# untitled.net
KiCad netlist of a schematic drawn in EAGLE
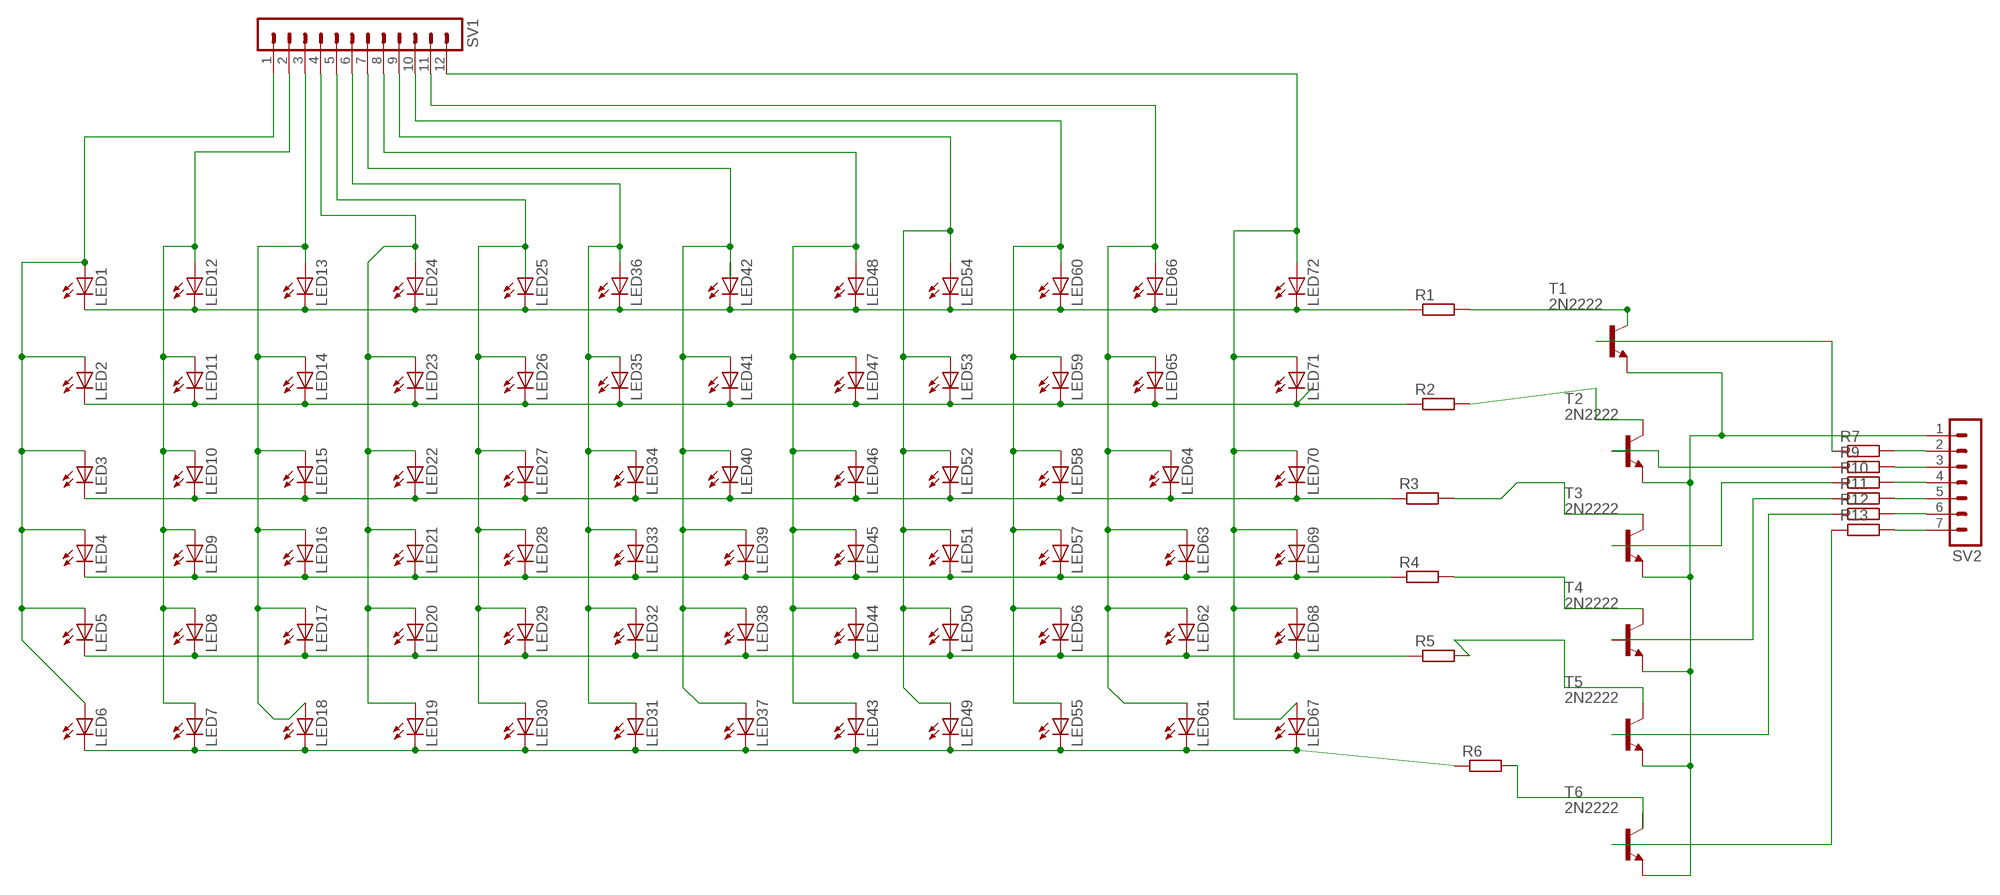
[diagram p0: schematic, sheet 1]

(export (version "E")
  (design (tool "Eeschema 10.0.6"))
  (components
    (comp (ref "LED1")
      (value "LED5MM")
      (footprint "eagle-import:LED5MM")
      (libsource (lib "eagle-import") (part "LED5MM"))
    )
    (comp (ref "LED2")
      (value "LED5MM")
      (footprint "eagle-import:LED5MM")
      (libsource (lib "eagle-import") (part "LED5MM"))
    )
    (comp (ref "LED3")
      (value "LED5MM")
      (footprint "eagle-import:LED5MM")
      (libsource (lib "eagle-import") (part "LED5MM"))
    )
    (comp (ref "LED4")
      (value "LED5MM")
      (footprint "eagle-import:LED5MM")
      (libsource (lib "eagle-import") (part "LED5MM"))
    )
    (comp (ref "LED5")
      (value "LED5MM")
      (footprint "eagle-import:LED5MM")
      (libsource (lib "eagle-import") (part "LED5MM"))
    )
    (comp (ref "LED6")
      (value "LED5MM")
      (footprint "eagle-import:LED5MM")
      (libsource (lib "eagle-import") (part "LED5MM"))
    )
    (comp (ref "LED7")
      (value "LED5MM")
      (footprint "eagle-import:LED5MM")
      (libsource (lib "eagle-import") (part "LED5MM"))
    )
    (comp (ref "LED8")
      (value "LED5MM")
      (footprint "eagle-import:LED5MM")
      (libsource (lib "eagle-import") (part "LED5MM"))
    )
    (comp (ref "LED9")
      (value "LED5MM")
      (footprint "eagle-import:LED5MM")
      (libsource (lib "eagle-import") (part "LED5MM"))
    )
    (comp (ref "LED10")
      (value "LED5MM")
      (footprint "eagle-import:LED5MM")
      (libsource (lib "eagle-import") (part "LED5MM"))
    )
    (comp (ref "LED11")
      (value "LED5MM")
      (footprint "eagle-import:LED5MM")
      (libsource (lib "eagle-import") (part "LED5MM"))
    )
    (comp (ref "LED12")
      (value "LED5MM")
      (footprint "eagle-import:LED5MM")
      (libsource (lib "eagle-import") (part "LED5MM"))
    )
    (comp (ref "LED13")
      (value "LED5MM")
      (footprint "eagle-import:LED5MM")
      (libsource (lib "eagle-import") (part "LED5MM"))
    )
    (comp (ref "LED14")
      (value "LED5MM")
      (footprint "eagle-import:LED5MM")
      (libsource (lib "eagle-import") (part "LED5MM"))
    )
    (comp (ref "LED15")
      (value "LED5MM")
      (footprint "eagle-import:LED5MM")
      (libsource (lib "eagle-import") (part "LED5MM"))
    )
    (comp (ref "LED16")
      (value "LED5MM")
      (footprint "eagle-import:LED5MM")
      (libsource (lib "eagle-import") (part "LED5MM"))
    )
    (comp (ref "LED17")
      (value "LED5MM")
      (footprint "eagle-import:LED5MM")
      (libsource (lib "eagle-import") (part "LED5MM"))
    )
    (comp (ref "LED18")
      (value "LED5MM")
      (footprint "eagle-import:LED5MM")
      (libsource (lib "eagle-import") (part "LED5MM"))
    )
    (comp (ref "LED19")
      (value "LED5MM")
      (footprint "eagle-import:LED5MM")
      (libsource (lib "eagle-import") (part "LED5MM"))
    )
    (comp (ref "LED20")
      (value "LED5MM")
      (footprint "eagle-import:LED5MM")
      (libsource (lib "eagle-import") (part "LED5MM"))
    )
    (comp (ref "LED21")
      (value "LED5MM")
      (footprint "eagle-import:LED5MM")
      (libsource (lib "eagle-import") (part "LED5MM"))
    )
    (comp (ref "LED22")
      (value "LED5MM")
      (footprint "eagle-import:LED5MM")
      (libsource (lib "eagle-import") (part "LED5MM"))
    )
    (comp (ref "LED23")
      (value "LED5MM")
      (footprint "eagle-import:LED5MM")
      (libsource (lib "eagle-import") (part "LED5MM"))
    )
    (comp (ref "LED24")
      (value "LED5MM")
      (footprint "eagle-import:LED5MM")
      (libsource (lib "eagle-import") (part "LED5MM"))
    )
    (comp (ref "LED25")
      (value "LED5MM")
      (footprint "eagle-import:LED5MM")
      (libsource (lib "eagle-import") (part "LED5MM"))
    )
    (comp (ref "LED26")
      (value "LED5MM")
      (footprint "eagle-import:LED5MM")
      (libsource (lib "eagle-import") (part "LED5MM"))
    )
    (comp (ref "LED27")
      (value "LED5MM")
      (footprint "eagle-import:LED5MM")
      (libsource (lib "eagle-import") (part "LED5MM"))
    )
    (comp (ref "LED28")
      (value "LED5MM")
      (footprint "eagle-import:LED5MM")
      (libsource (lib "eagle-import") (part "LED5MM"))
    )
    (comp (ref "LED29")
      (value "LED5MM")
      (footprint "eagle-import:LED5MM")
      (libsource (lib "eagle-import") (part "LED5MM"))
    )
    (comp (ref "LED30")
      (value "LED5MM")
      (footprint "eagle-import:LED5MM")
      (libsource (lib "eagle-import") (part "LED5MM"))
    )
    (comp (ref "LED31")
      (value "LED5MM")
      (footprint "eagle-import:LED5MM")
      (libsource (lib "eagle-import") (part "LED5MM"))
    )
    (comp (ref "LED32")
      (value "LED5MM")
      (footprint "eagle-import:LED5MM")
      (libsource (lib "eagle-import") (part "LED5MM"))
    )
    (comp (ref "LED33")
      (value "LED5MM")
      (footprint "eagle-import:LED5MM")
      (libsource (lib "eagle-import") (part "LED5MM"))
    )
    (comp (ref "LED34")
      (value "LED5MM")
      (footprint "eagle-import:LED5MM")
      (libsource (lib "eagle-import") (part "LED5MM"))
    )
    (comp (ref "LED35")
      (value "LED5MM")
      (footprint "eagle-import:LED5MM")
      (libsource (lib "eagle-import") (part "LED5MM"))
    )
    (comp (ref "LED36")
      (value "LED5MM")
      (footprint "eagle-import:LED5MM")
      (libsource (lib "eagle-import") (part "LED5MM"))
    )
    (comp (ref "LED37")
      (value "LED5MM")
      (footprint "eagle-import:LED5MM")
      (libsource (lib "eagle-import") (part "LED5MM"))
    )
    (comp (ref "LED38")
      (value "LED5MM")
      (footprint "eagle-import:LED5MM")
      (libsource (lib "eagle-import") (part "LED5MM"))
    )
    (comp (ref "LED39")
      (value "LED5MM")
      (footprint "eagle-import:LED5MM")
      (libsource (lib "eagle-import") (part "LED5MM"))
    )
    (comp (ref "LED40")
      (value "LED5MM")
      (footprint "eagle-import:LED5MM")
      (libsource (lib "eagle-import") (part "LED5MM"))
    )
    (comp (ref "LED41")
      (value "LED5MM")
      (footprint "eagle-import:LED5MM")
      (libsource (lib "eagle-import") (part "LED5MM"))
    )
    (comp (ref "LED42")
      (value "LED5MM")
      (footprint "eagle-import:LED5MM")
      (libsource (lib "eagle-import") (part "LED5MM"))
    )
    (comp (ref "LED43")
      (value "LED5MM")
      (footprint "eagle-import:LED5MM")
      (libsource (lib "eagle-import") (part "LED5MM"))
    )
    (comp (ref "LED44")
      (value "LED5MM")
      (footprint "eagle-import:LED5MM")
      (libsource (lib "eagle-import") (part "LED5MM"))
    )
    (comp (ref "LED45")
      (value "LED5MM")
      (footprint "eagle-import:LED5MM")
      (libsource (lib "eagle-import") (part "LED5MM"))
    )
    (comp (ref "LED46")
      (value "LED5MM")
      (footprint "eagle-import:LED5MM")
      (libsource (lib "eagle-import") (part "LED5MM"))
    )
    (comp (ref "LED47")
      (value "LED5MM")
      (footprint "eagle-import:LED5MM")
      (libsource (lib "eagle-import") (part "LED5MM"))
    )
    (comp (ref "LED48")
      (value "LED5MM")
      (footprint "eagle-import:LED5MM")
      (libsource (lib "eagle-import") (part "LED5MM"))
    )
    (comp (ref "LED49")
      (value "LED5MM")
      (footprint "eagle-import:LED5MM")
      (libsource (lib "eagle-import") (part "LED5MM"))
    )
    (comp (ref "LED50")
      (value "LED5MM")
      (footprint "eagle-import:LED5MM")
      (libsource (lib "eagle-import") (part "LED5MM"))
    )
    (comp (ref "LED51")
      (value "LED5MM")
      (footprint "eagle-import:LED5MM")
      (libsource (lib "eagle-import") (part "LED5MM"))
    )
    (comp (ref "LED52")
      (value "LED5MM")
      (footprint "eagle-import:LED5MM")
      (libsource (lib "eagle-import") (part "LED5MM"))
    )
    (comp (ref "LED53")
      (value "LED5MM")
      (footprint "eagle-import:LED5MM")
      (libsource (lib "eagle-import") (part "LED5MM"))
    )
    (comp (ref "LED54")
      (value "LED5MM")
      (footprint "eagle-import:LED5MM")
      (libsource (lib "eagle-import") (part "LED5MM"))
    )
    (comp (ref "LED55")
      (value "LED5MM")
      (footprint "eagle-import:LED5MM")
      (libsource (lib "eagle-import") (part "LED5MM"))
    )
    (comp (ref "LED56")
      (value "LED5MM")
      (footprint "eagle-import:LED5MM")
      (libsource (lib "eagle-import") (part "LED5MM"))
    )
    (comp (ref "LED57")
      (value "LED5MM")
      (footprint "eagle-import:LED5MM")
      (libsource (lib "eagle-import") (part "LED5MM"))
    )
    (comp (ref "LED58")
      (value "LED5MM")
      (footprint "eagle-import:LED5MM")
      (libsource (lib "eagle-import") (part "LED5MM"))
    )
    (comp (ref "LED59")
      (value "LED5MM")
      (footprint "eagle-import:LED5MM")
      (libsource (lib "eagle-import") (part "LED5MM"))
    )
    (comp (ref "LED60")
      (value "LED5MM")
      (footprint "eagle-import:LED5MM")
      (libsource (lib "eagle-import") (part "LED5MM"))
    )
    (comp (ref "LED61")
      (value "LED5MM")
      (footprint "eagle-import:LED5MM")
      (libsource (lib "eagle-import") (part "LED5MM"))
    )
    (comp (ref "LED62")
      (value "LED5MM")
      (footprint "eagle-import:LED5MM")
      (libsource (lib "eagle-import") (part "LED5MM"))
    )
    (comp (ref "LED63")
      (value "LED5MM")
      (footprint "eagle-import:LED5MM")
      (libsource (lib "eagle-import") (part "LED5MM"))
    )
    (comp (ref "LED64")
      (value "LED5MM")
      (footprint "eagle-import:LED5MM")
      (libsource (lib "eagle-import") (part "LED5MM"))
    )
    (comp (ref "LED65")
      (value "LED5MM")
      (footprint "eagle-import:LED5MM")
      (libsource (lib "eagle-import") (part "LED5MM"))
    )
    (comp (ref "LED66")
      (value "LED5MM")
      (footprint "eagle-import:LED5MM")
      (libsource (lib "eagle-import") (part "LED5MM"))
    )
    (comp (ref "LED67")
      (value "LED5MM")
      (footprint "eagle-import:LED5MM")
      (libsource (lib "eagle-import") (part "LED5MM"))
    )
    (comp (ref "LED68")
      (value "LED5MM")
      (footprint "eagle-import:LED5MM")
      (libsource (lib "eagle-import") (part "LED5MM"))
    )
    (comp (ref "LED69")
      (value "LED5MM")
      (footprint "eagle-import:LED5MM")
      (libsource (lib "eagle-import") (part "LED5MM"))
    )
    (comp (ref "LED70")
      (value "LED5MM")
      (footprint "eagle-import:LED5MM")
      (libsource (lib "eagle-import") (part "LED5MM"))
    )
    (comp (ref "LED71")
      (value "LED5MM")
      (footprint "eagle-import:LED5MM")
      (libsource (lib "eagle-import") (part "LED5MM"))
    )
    (comp (ref "LED72")
      (value "LED5MM")
      (footprint "eagle-import:LED5MM")
      (libsource (lib "eagle-import") (part "LED5MM"))
    )
    (comp (ref "R1")
      (value "R-EU_0207/10")
      (footprint "eagle-import:0207_10")
      (libsource (lib "eagle-import") (part "R-EU_0207/10"))
    )
    (comp (ref "R2")
      (value "R-EU_0207/10")
      (footprint "eagle-import:0207_10")
      (libsource (lib "eagle-import") (part "R-EU_0207/10"))
    )
    (comp (ref "R3")
      (value "R-EU_0207/10")
      (footprint "eagle-import:0207_10")
      (libsource (lib "eagle-import") (part "R-EU_0207/10"))
    )
    (comp (ref "R4")
      (value "R-EU_0207/10")
      (footprint "eagle-import:0207_10")
      (libsource (lib "eagle-import") (part "R-EU_0207/10"))
    )
    (comp (ref "R5")
      (value "R-EU_0207/10")
      (footprint "eagle-import:0207_10")
      (libsource (lib "eagle-import") (part "R-EU_0207/10"))
    )
    (comp (ref "R6")
      (value "R-EU_0207/10")
      (footprint "eagle-import:0207_10")
      (libsource (lib "eagle-import") (part "R-EU_0207/10"))
    )
    (comp (ref "R7")
      (value "R-EU_0207/10")
      (footprint "eagle-import:0207_10")
      (libsource (lib "eagle-import") (part "R-EU_0207/10"))
    )
    (comp (ref "R9")
      (value "R-EU_0207/10")
      (footprint "eagle-import:0207_10")
      (libsource (lib "eagle-import") (part "R-EU_0207/10"))
    )
    (comp (ref "R10")
      (value "R-EU_0207/10")
      (footprint "eagle-import:0207_10")
      (libsource (lib "eagle-import") (part "R-EU_0207/10"))
    )
    (comp (ref "R11")
      (value "R-EU_0207/10")
      (footprint "eagle-import:0207_10")
      (libsource (lib "eagle-import") (part "R-EU_0207/10"))
    )
    (comp (ref "R12")
      (value "R-EU_0207/10")
      (footprint "eagle-import:0207_10")
      (libsource (lib "eagle-import") (part "R-EU_0207/10"))
    )
    (comp (ref "R13")
      (value "R-EU_0207/10")
      (footprint "eagle-import:0207_10")
      (libsource (lib "eagle-import") (part "R-EU_0207/10"))
    )
    (comp (ref "SV1")
      (value "MA12-1")
      (footprint "eagle-import:MA12-1")
      (libsource (lib "eagle-import") (part "MA12-1"))
    )
    (comp (ref "SV2")
      (value "MA07-1")
      (footprint "eagle-import:MA07-1")
      (libsource (lib "eagle-import") (part "MA07-1"))
    )
    (comp (ref "T1")
      (value "2N2222")
      (footprint "eagle-import:TO18")
      (libsource (lib "eagle-import") (part "2N2222"))
    )
    (comp (ref "T2")
      (value "2N2222")
      (footprint "eagle-import:TO18")
      (libsource (lib "eagle-import") (part "2N2222"))
    )
    (comp (ref "T3")
      (value "2N2222")
      (footprint "eagle-import:TO18")
      (libsource (lib "eagle-import") (part "2N2222"))
    )
    (comp (ref "T4")
      (value "2N2222")
      (footprint "eagle-import:TO18")
      (libsource (lib "eagle-import") (part "2N2222"))
    )
    (comp (ref "T5")
      (value "2N2222")
      (footprint "eagle-import:TO18")
      (libsource (lib "eagle-import") (part "2N2222"))
    )
    (comp (ref "T6")
      (value "2N2222")
      (footprint "eagle-import:TO18")
      (libsource (lib "eagle-import") (part "2N2222"))
    )
  )
  (nets
    (net (code "1") (name "Net-(LED1-C)") (class "Default")
      (node (ref "LED1") (pin "K") (pinfunction "C_K") (pintype "passive"))
      (node (ref "LED12") (pin "K") (pinfunction "C_K") (pintype "passive"))
      (node (ref "LED13") (pin "K") (pinfunction "C_K") (pintype "passive"))
      (node (ref "LED24") (pin "K") (pinfunction "C_K") (pintype "passive"))
      (node (ref "LED25") (pin "K") (pinfunction "C_K") (pintype "passive"))
      (node (ref "LED36") (pin "K") (pinfunction "C_K") (pintype "passive"))
      (node (ref "LED42") (pin "K") (pinfunction "C_K") (pintype "passive"))
      (node (ref "LED48") (pin "K") (pinfunction "C_K") (pintype "passive"))
      (node (ref "LED54") (pin "K") (pinfunction "C_K") (pintype "passive"))
      (node (ref "LED60") (pin "K") (pinfunction "C_K") (pintype "passive"))
      (node (ref "LED66") (pin "K") (pinfunction "C_K") (pintype "passive"))
      (node (ref "LED72") (pin "K") (pinfunction "C_K") (pintype "passive"))
      (node (ref "R1") (pin "1") (pinfunction "1_1") (pintype "passive"))
    )
    (net (code "2") (name "Net-(LED1-PadA)") (class "Default")
      (node (ref "LED1") (pin "A") (pinfunction "A_A") (pintype "passive"))
      (node (ref "LED2") (pin "A") (pinfunction "A_A") (pintype "passive"))
      (node (ref "LED3") (pin "A") (pinfunction "A_A") (pintype "passive"))
      (node (ref "LED4") (pin "A") (pinfunction "A_A") (pintype "passive"))
      (node (ref "LED5") (pin "A") (pinfunction "A_A") (pintype "passive"))
      (node (ref "LED6") (pin "A") (pinfunction "A_A") (pintype "passive"))
      (node (ref "SV1") (pin "1") (pinfunction "1_1") (pintype "passive"))
    )
    (net (code "3") (name "Net-(LED10-C)") (class "Default")
      (node (ref "LED10") (pin "K") (pinfunction "C_K") (pintype "passive"))
      (node (ref "LED15") (pin "K") (pinfunction "C_K") (pintype "passive"))
      (node (ref "LED22") (pin "K") (pinfunction "C_K") (pintype "passive"))
      (node (ref "LED27") (pin "K") (pinfunction "C_K") (pintype "passive"))
      (node (ref "LED3") (pin "K") (pinfunction "C_K") (pintype "passive"))
      (node (ref "LED34") (pin "K") (pinfunction "C_K") (pintype "passive"))
      (node (ref "LED40") (pin "K") (pinfunction "C_K") (pintype "passive"))
      (node (ref "LED46") (pin "K") (pinfunction "C_K") (pintype "passive"))
      (node (ref "LED52") (pin "K") (pinfunction "C_K") (pintype "passive"))
      (node (ref "LED58") (pin "K") (pinfunction "C_K") (pintype "passive"))
      (node (ref "LED64") (pin "K") (pinfunction "C_K") (pintype "passive"))
      (node (ref "LED70") (pin "K") (pinfunction "C_K") (pintype "passive"))
      (node (ref "R3") (pin "1") (pinfunction "1_1") (pintype "passive"))
    )
    (net (code "4") (name "Net-(LED10-PadA)") (class "Default")
      (node (ref "LED10") (pin "A") (pinfunction "A_A") (pintype "passive"))
      (node (ref "LED11") (pin "A") (pinfunction "A_A") (pintype "passive"))
      (node (ref "LED12") (pin "A") (pinfunction "A_A") (pintype "passive"))
      (node (ref "LED7") (pin "A") (pinfunction "A_A") (pintype "passive"))
      (node (ref "LED8") (pin "A") (pinfunction "A_A") (pintype "passive"))
      (node (ref "LED9") (pin "A") (pinfunction "A_A") (pintype "passive"))
      (node (ref "SV1") (pin "2") (pinfunction "2_2") (pintype "passive"))
    )
    (net (code "5") (name "Net-(LED11-C)") (class "Default")
      (node (ref "LED11") (pin "K") (pinfunction "C_K") (pintype "passive"))
      (node (ref "LED14") (pin "K") (pinfunction "C_K") (pintype "passive"))
      (node (ref "LED2") (pin "K") (pinfunction "C_K") (pintype "passive"))
      (node (ref "LED23") (pin "K") (pinfunction "C_K") (pintype "passive"))
      (node (ref "LED26") (pin "K") (pinfunction "C_K") (pintype "passive"))
      (node (ref "LED35") (pin "K") (pinfunction "C_K") (pintype "passive"))
      (node (ref "LED41") (pin "K") (pinfunction "C_K") (pintype "passive"))
      (node (ref "LED47") (pin "K") (pinfunction "C_K") (pintype "passive"))
      (node (ref "LED53") (pin "K") (pinfunction "C_K") (pintype "passive"))
      (node (ref "LED59") (pin "K") (pinfunction "C_K") (pintype "passive"))
      (node (ref "LED65") (pin "K") (pinfunction "C_K") (pintype "passive"))
      (node (ref "LED71") (pin "K") (pinfunction "C_K") (pintype "passive"))
      (node (ref "R2") (pin "1") (pinfunction "1_1") (pintype "passive"))
    )
    (net (code "6") (name "Net-(LED13-PadA)") (class "Default")
      (node (ref "LED13") (pin "A") (pinfunction "A_A") (pintype "passive"))
      (node (ref "LED14") (pin "A") (pinfunction "A_A") (pintype "passive"))
      (node (ref "LED15") (pin "A") (pinfunction "A_A") (pintype "passive"))
      (node (ref "LED16") (pin "A") (pinfunction "A_A") (pintype "passive"))
      (node (ref "LED17") (pin "A") (pinfunction "A_A") (pintype "passive"))
      (node (ref "LED18") (pin "A") (pinfunction "A_A") (pintype "passive"))
      (node (ref "SV1") (pin "3") (pinfunction "3_3") (pintype "passive"))
    )
    (net (code "7") (name "Net-(LED16-C)") (class "Default")
      (node (ref "LED16") (pin "K") (pinfunction "C_K") (pintype "passive"))
      (node (ref "LED21") (pin "K") (pinfunction "C_K") (pintype "passive"))
      (node (ref "LED28") (pin "K") (pinfunction "C_K") (pintype "passive"))
      (node (ref "LED33") (pin "K") (pinfunction "C_K") (pintype "passive"))
      (node (ref "LED39") (pin "K") (pinfunction "C_K") (pintype "passive"))
      (node (ref "LED4") (pin "K") (pinfunction "C_K") (pintype "passive"))
      (node (ref "LED45") (pin "K") (pinfunction "C_K") (pintype "passive"))
      (node (ref "LED51") (pin "K") (pinfunction "C_K") (pintype "passive"))
      (node (ref "LED57") (pin "K") (pinfunction "C_K") (pintype "passive"))
      (node (ref "LED63") (pin "K") (pinfunction "C_K") (pintype "passive"))
      (node (ref "LED69") (pin "K") (pinfunction "C_K") (pintype "passive"))
      (node (ref "LED9") (pin "K") (pinfunction "C_K") (pintype "passive"))
      (node (ref "R4") (pin "1") (pinfunction "1_1") (pintype "passive"))
    )
    (net (code "8") (name "Net-(LED17-C)") (class "Default")
      (node (ref "LED17") (pin "K") (pinfunction "C_K") (pintype "passive"))
      (node (ref "LED20") (pin "K") (pinfunction "C_K") (pintype "passive"))
      (node (ref "LED29") (pin "K") (pinfunction "C_K") (pintype "passive"))
      (node (ref "LED32") (pin "K") (pinfunction "C_K") (pintype "passive"))
      (node (ref "LED38") (pin "K") (pinfunction "C_K") (pintype "passive"))
      (node (ref "LED44") (pin "K") (pinfunction "C_K") (pintype "passive"))
      (node (ref "LED5") (pin "K") (pinfunction "C_K") (pintype "passive"))
      (node (ref "LED50") (pin "K") (pinfunction "C_K") (pintype "passive"))
      (node (ref "LED56") (pin "K") (pinfunction "C_K") (pintype "passive"))
      (node (ref "LED62") (pin "K") (pinfunction "C_K") (pintype "passive"))
      (node (ref "LED68") (pin "K") (pinfunction "C_K") (pintype "passive"))
      (node (ref "LED8") (pin "K") (pinfunction "C_K") (pintype "passive"))
      (node (ref "R5") (pin "1") (pinfunction "1_1") (pintype "passive"))
    )
    (net (code "9") (name "Net-(LED18-C)") (class "Default")
      (node (ref "LED18") (pin "K") (pinfunction "C_K") (pintype "passive"))
      (node (ref "LED19") (pin "K") (pinfunction "C_K") (pintype "passive"))
      (node (ref "LED30") (pin "K") (pinfunction "C_K") (pintype "passive"))
      (node (ref "LED31") (pin "K") (pinfunction "C_K") (pintype "passive"))
      (node (ref "LED37") (pin "K") (pinfunction "C_K") (pintype "passive"))
      (node (ref "LED43") (pin "K") (pinfunction "C_K") (pintype "passive"))
      (node (ref "LED49") (pin "K") (pinfunction "C_K") (pintype "passive"))
      (node (ref "LED55") (pin "K") (pinfunction "C_K") (pintype "passive"))
      (node (ref "LED6") (pin "K") (pinfunction "C_K") (pintype "passive"))
      (node (ref "LED61") (pin "K") (pinfunction "C_K") (pintype "passive"))
      (node (ref "LED67") (pin "K") (pinfunction "C_K") (pintype "passive"))
      (node (ref "LED7") (pin "K") (pinfunction "C_K") (pintype "passive"))
      (node (ref "R6") (pin "1") (pinfunction "1_1") (pintype "passive"))
    )
    (net (code "10") (name "Net-(LED19-PadA)") (class "Default")
      (node (ref "LED19") (pin "A") (pinfunction "A_A") (pintype "passive"))
      (node (ref "LED20") (pin "A") (pinfunction "A_A") (pintype "passive"))
      (node (ref "LED21") (pin "A") (pinfunction "A_A") (pintype "passive"))
      (node (ref "LED22") (pin "A") (pinfunction "A_A") (pintype "passive"))
      (node (ref "LED23") (pin "A") (pinfunction "A_A") (pintype "passive"))
      (node (ref "LED24") (pin "A") (pinfunction "A_A") (pintype "passive"))
      (node (ref "SV1") (pin "4") (pinfunction "4_4") (pintype "passive"))
    )
    (net (code "11") (name "Net-(LED25-PadA)") (class "Default")
      (node (ref "LED25") (pin "A") (pinfunction "A_A") (pintype "passive"))
      (node (ref "LED26") (pin "A") (pinfunction "A_A") (pintype "passive"))
      (node (ref "LED27") (pin "A") (pinfunction "A_A") (pintype "passive"))
      (node (ref "LED28") (pin "A") (pinfunction "A_A") (pintype "passive"))
      (node (ref "LED29") (pin "A") (pinfunction "A_A") (pintype "passive"))
      (node (ref "LED30") (pin "A") (pinfunction "A_A") (pintype "passive"))
      (node (ref "SV1") (pin "5") (pinfunction "5_5") (pintype "passive"))
    )
    (net (code "12") (name "Net-(LED31-PadA)") (class "Default")
      (node (ref "LED31") (pin "A") (pinfunction "A_A") (pintype "passive"))
      (node (ref "LED32") (pin "A") (pinfunction "A_A") (pintype "passive"))
      (node (ref "LED33") (pin "A") (pinfunction "A_A") (pintype "passive"))
      (node (ref "LED34") (pin "A") (pinfunction "A_A") (pintype "passive"))
      (node (ref "LED35") (pin "A") (pinfunction "A_A") (pintype "passive"))
      (node (ref "LED36") (pin "A") (pinfunction "A_A") (pintype "passive"))
      (node (ref "SV1") (pin "6") (pinfunction "6_6") (pintype "passive"))
    )
    (net (code "13") (name "Net-(LED37-PadA)") (class "Default")
      (node (ref "LED37") (pin "A") (pinfunction "A_A") (pintype "passive"))
      (node (ref "LED38") (pin "A") (pinfunction "A_A") (pintype "passive"))
      (node (ref "LED39") (pin "A") (pinfunction "A_A") (pintype "passive"))
      (node (ref "LED40") (pin "A") (pinfunction "A_A") (pintype "passive"))
      (node (ref "LED41") (pin "A") (pinfunction "A_A") (pintype "passive"))
      (node (ref "LED42") (pin "A") (pinfunction "A_A") (pintype "passive"))
      (node (ref "SV1") (pin "7") (pinfunction "7_7") (pintype "passive"))
    )
    (net (code "14") (name "Net-(LED43-PadA)") (class "Default")
      (node (ref "LED43") (pin "A") (pinfunction "A_A") (pintype "passive"))
      (node (ref "LED44") (pin "A") (pinfunction "A_A") (pintype "passive"))
      (node (ref "LED45") (pin "A") (pinfunction "A_A") (pintype "passive"))
      (node (ref "LED46") (pin "A") (pinfunction "A_A") (pintype "passive"))
      (node (ref "LED47") (pin "A") (pinfunction "A_A") (pintype "passive"))
      (node (ref "LED48") (pin "A") (pinfunction "A_A") (pintype "passive"))
      (node (ref "SV1") (pin "8") (pinfunction "8_8") (pintype "passive"))
    )
    (net (code "15") (name "Net-(LED49-PadA)") (class "Default")
      (node (ref "LED49") (pin "A") (pinfunction "A_A") (pintype "passive"))
      (node (ref "LED50") (pin "A") (pinfunction "A_A") (pintype "passive"))
      (node (ref "LED51") (pin "A") (pinfunction "A_A") (pintype "passive"))
      (node (ref "LED52") (pin "A") (pinfunction "A_A") (pintype "passive"))
      (node (ref "LED53") (pin "A") (pinfunction "A_A") (pintype "passive"))
      (node (ref "LED54") (pin "A") (pinfunction "A_A") (pintype "passive"))
      (node (ref "SV1") (pin "9") (pinfunction "9_9") (pintype "passive"))
    )
    (net (code "16") (name "Net-(LED55-PadA)") (class "Default")
      (node (ref "LED55") (pin "A") (pinfunction "A_A") (pintype "passive"))
      (node (ref "LED56") (pin "A") (pinfunction "A_A") (pintype "passive"))
      (node (ref "LED57") (pin "A") (pinfunction "A_A") (pintype "passive"))
      (node (ref "LED58") (pin "A") (pinfunction "A_A") (pintype "passive"))
      (node (ref "LED59") (pin "A") (pinfunction "A_A") (pintype "passive"))
      (node (ref "LED60") (pin "A") (pinfunction "A_A") (pintype "passive"))
      (node (ref "SV1") (pin "10") (pinfunction "10_10") (pintype "passive"))
    )
    (net (code "17") (name "Net-(LED61-PadA)") (class "Default")
      (node (ref "LED61") (pin "A") (pinfunction "A_A") (pintype "passive"))
      (node (ref "LED62") (pin "A") (pinfunction "A_A") (pintype "passive"))
      (node (ref "LED63") (pin "A") (pinfunction "A_A") (pintype "passive"))
      (node (ref "LED64") (pin "A") (pinfunction "A_A") (pintype "passive"))
      (node (ref "LED65") (pin "A") (pinfunction "A_A") (pintype "passive"))
      (node (ref "LED66") (pin "A") (pinfunction "A_A") (pintype "passive"))
      (node (ref "SV1") (pin "11") (pinfunction "11_11") (pintype "passive"))
    )
    (net (code "18") (name "Net-(LED67-PadA)") (class "Default")
      (node (ref "LED67") (pin "A") (pinfunction "A_A") (pintype "passive"))
      (node (ref "LED68") (pin "A") (pinfunction "A_A") (pintype "passive"))
      (node (ref "LED69") (pin "A") (pinfunction "A_A") (pintype "passive"))
      (node (ref "LED70") (pin "A") (pinfunction "A_A") (pintype "passive"))
      (node (ref "LED71") (pin "A") (pinfunction "A_A") (pintype "passive"))
      (node (ref "LED72") (pin "A") (pinfunction "A_A") (pintype "passive"))
      (node (ref "SV1") (pin "12") (pinfunction "12_12") (pintype "passive"))
    )
    (net (code "19") (name "Net-(R7-Pad2)") (class "Default")
      (node (ref "R7") (pin "2") (pinfunction "2_2") (pintype "passive"))
      (node (ref "SV2") (pin "2") (pinfunction "2_2") (pintype "passive"))
    )
    (net (code "20") (name "Net-(R9-Pad2)") (class "Default")
      (node (ref "R9") (pin "2") (pinfunction "2_2") (pintype "passive"))
      (node (ref "SV2") (pin "3") (pinfunction "3_3") (pintype "passive"))
    )
    (net (code "21") (name "Net-(R10-Pad2)") (class "Default")
      (node (ref "R10") (pin "2") (pinfunction "2_2") (pintype "passive"))
      (node (ref "SV2") (pin "4") (pinfunction "4_4") (pintype "passive"))
    )
    (net (code "22") (name "Net-(R11-Pad2)") (class "Default")
      (node (ref "R11") (pin "2") (pinfunction "2_2") (pintype "passive"))
      (node (ref "SV2") (pin "5") (pinfunction "5_5") (pintype "passive"))
    )
    (net (code "23") (name "Net-(R12-Pad2)") (class "Default")
      (node (ref "R12") (pin "2") (pinfunction "2_2") (pintype "passive"))
      (node (ref "SV2") (pin "6") (pinfunction "6_6") (pintype "passive"))
    )
    (net (code "24") (name "Net-(R13-Pad2)") (class "Default")
      (node (ref "R13") (pin "2") (pinfunction "2_2") (pintype "passive"))
      (node (ref "SV2") (pin "7") (pinfunction "7_7") (pintype "passive"))
    )
    (net (code "25") (name "Net-(T1-B)") (class "Default")
      (node (ref "R7") (pin "1") (pinfunction "1_1") (pintype "passive"))
      (node (ref "T1") (pin "2") (pinfunction "B_2") (pintype "passive"))
    )
    (net (code "26") (name "Net-(T1-C)") (class "Default")
      (node (ref "R1") (pin "2") (pinfunction "2_2") (pintype "passive"))
      (node (ref "T1") (pin "3") (pinfunction "C_3") (pintype "passive"))
    )
    (net (code "27") (name "Net-(T1-E)") (class "Default")
      (node (ref "SV2") (pin "1") (pinfunction "1_1") (pintype "passive"))
      (node (ref "T1") (pin "1") (pinfunction "E_1") (pintype "passive"))
      (node (ref "T2") (pin "1") (pinfunction "E_1") (pintype "passive"))
      (node (ref "T3") (pin "1") (pinfunction "E_1") (pintype "passive"))
      (node (ref "T4") (pin "1") (pinfunction "E_1") (pintype "passive"))
      (node (ref "T5") (pin "1") (pinfunction "E_1") (pintype "passive"))
      (node (ref "T6") (pin "1") (pinfunction "E_1") (pintype "passive"))
    )
    (net (code "28") (name "Net-(T2-B)") (class "Default")
      (node (ref "R9") (pin "1") (pinfunction "1_1") (pintype "passive"))
      (node (ref "T2") (pin "2") (pinfunction "B_2") (pintype "passive"))
    )
    (net (code "29") (name "Net-(T2-C)") (class "Default")
      (node (ref "R2") (pin "2") (pinfunction "2_2") (pintype "passive"))
      (node (ref "T2") (pin "3") (pinfunction "C_3") (pintype "passive"))
    )
    (net (code "30") (name "Net-(T3-B)") (class "Default")
      (node (ref "R10") (pin "1") (pinfunction "1_1") (pintype "passive"))
      (node (ref "T3") (pin "2") (pinfunction "B_2") (pintype "passive"))
    )
    (net (code "31") (name "Net-(T3-C)") (class "Default")
      (node (ref "R3") (pin "2") (pinfunction "2_2") (pintype "passive"))
      (node (ref "T3") (pin "3") (pinfunction "C_3") (pintype "passive"))
    )
    (net (code "32") (name "Net-(T4-B)") (class "Default")
      (node (ref "R11") (pin "1") (pinfunction "1_1") (pintype "passive"))
      (node (ref "T4") (pin "2") (pinfunction "B_2") (pintype "passive"))
    )
    (net (code "33") (name "Net-(T4-C)") (class "Default")
      (node (ref "R4") (pin "2") (pinfunction "2_2") (pintype "passive"))
      (node (ref "T4") (pin "3") (pinfunction "C_3") (pintype "passive"))
    )
    (net (code "34") (name "Net-(T5-B)") (class "Default")
      (node (ref "R12") (pin "1") (pinfunction "1_1") (pintype "passive"))
      (node (ref "T5") (pin "2") (pinfunction "B_2") (pintype "passive"))
    )
    (net (code "35") (name "Net-(T5-C)") (class "Default")
      (node (ref "R5") (pin "2") (pinfunction "2_2") (pintype "passive"))
      (node (ref "T5") (pin "3") (pinfunction "C_3") (pintype "passive"))
    )
    (net (code "36") (name "Net-(T6-B)") (class "Default")
      (node (ref "R13") (pin "1") (pinfunction "1_1") (pintype "passive"))
      (node (ref "T6") (pin "2") (pinfunction "B_2") (pintype "passive"))
    )
    (net (code "37") (name "Net-(T6-C)") (class "Default")
      (node (ref "R6") (pin "2") (pinfunction "2_2") (pintype "passive"))
      (node (ref "T6") (pin "3") (pinfunction "C_3") (pintype "passive"))
    )
  )
)
